# SparkFun_SSOP28-DIP-Adapter-v12.net
KiCad netlist of a schematic drawn in EAGLE
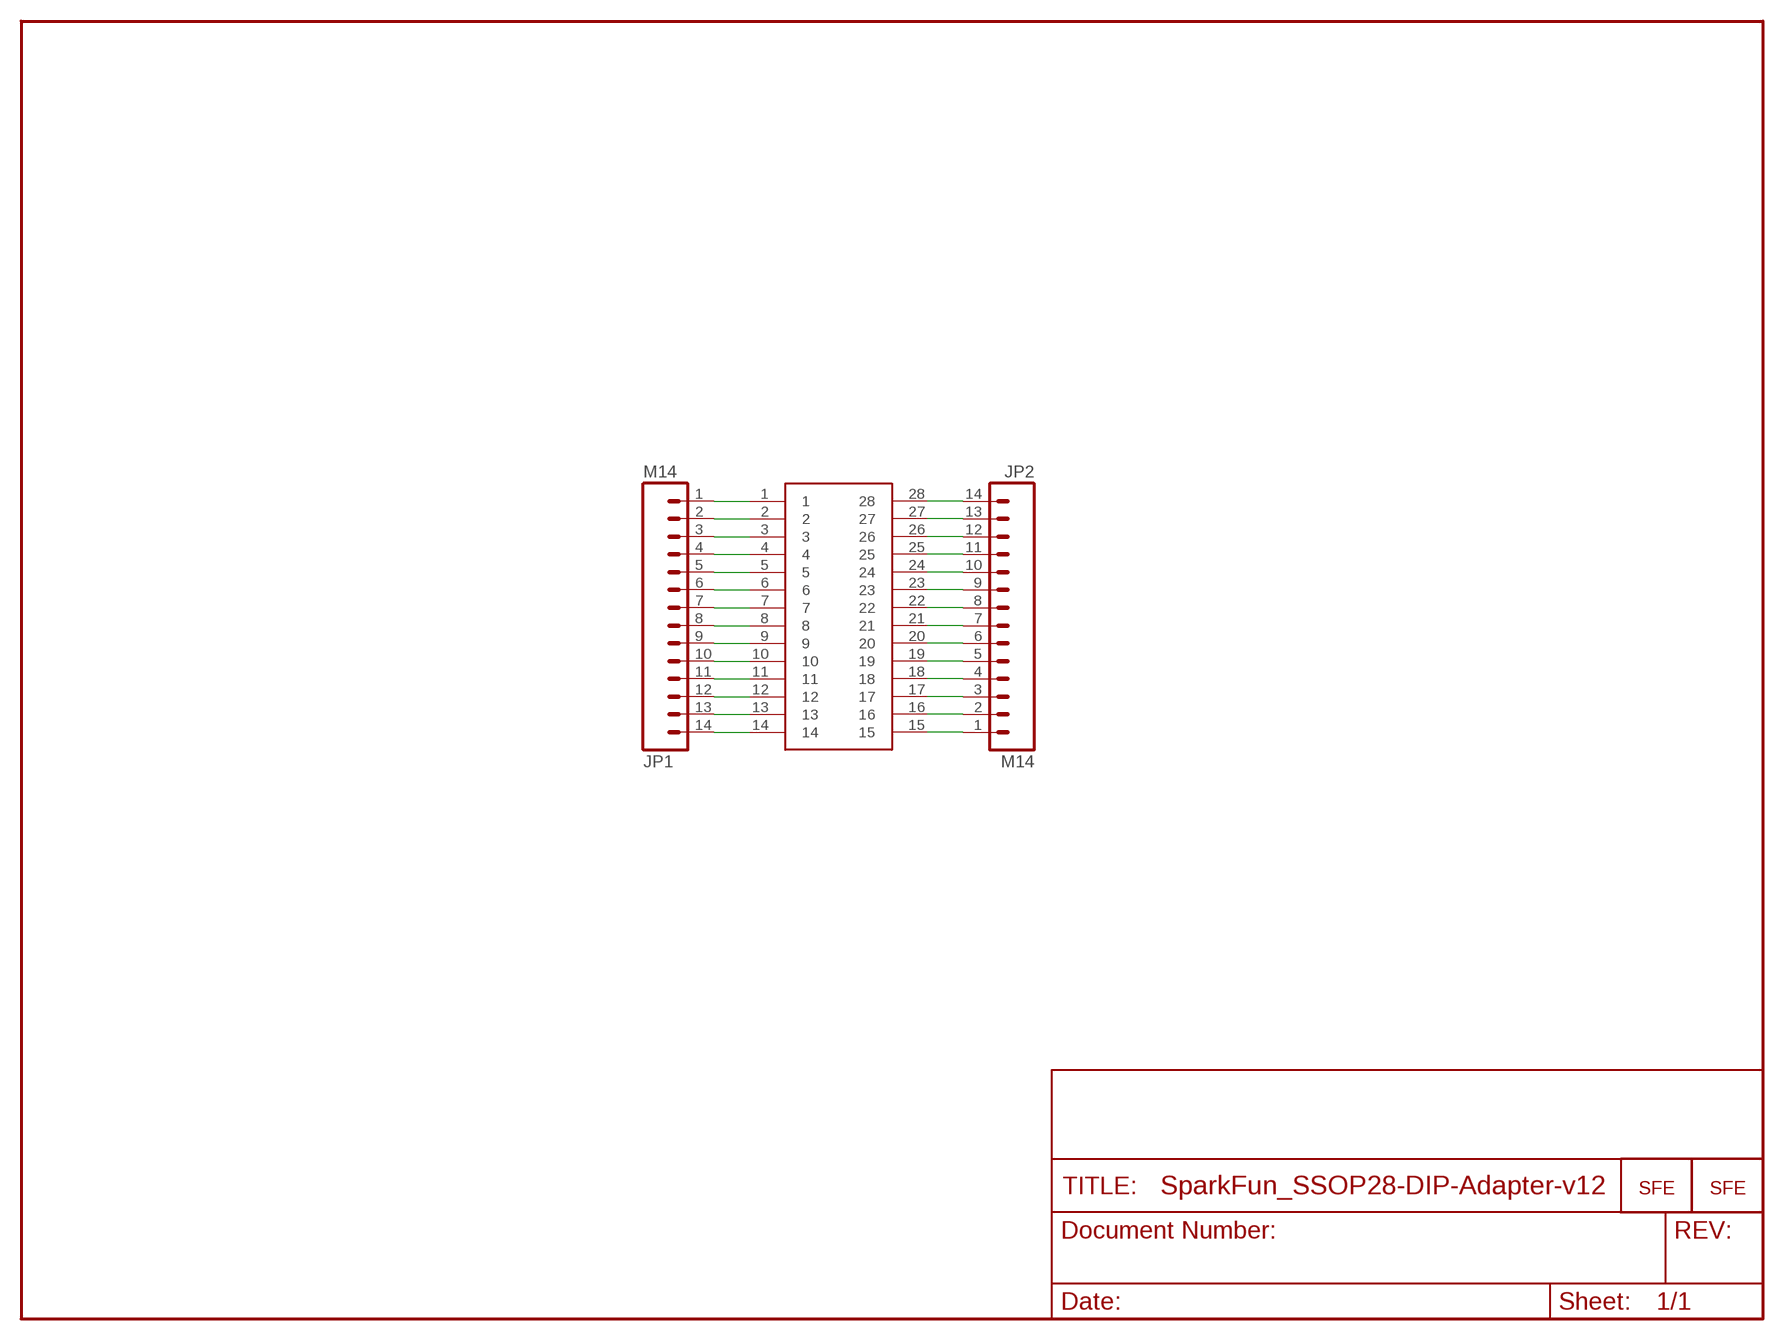
[diagram p0: schematic, sheet 1]

(export (version "E")
  (design (tool "Eeschema 10.0.6"))
  (components
    (comp (ref "JP1")
      (value "M14")
      (footprint "eagle-import:1X14")
      (libsource (lib "eagle-import") (part "M14"))
    )
    (comp (ref "JP2")
      (value "M14")
      (footprint "eagle-import:1X14")
      (libsource (lib "eagle-import") (part "M14"))
    )
    (comp (ref "U$1")
      (value "LOGO-SFESK")
      (footprint "eagle-import:SFE-LOGO-FLAME")
      (libsource (lib "eagle-import") (part "LOGO-SFESK"))
    )
    (comp (ref "U$2")
      (value "SSOP28")
      (footprint "eagle-import:SSOP28DB")
      (libsource (lib "eagle-import") (part "SSOP28"))
    )
    (comp (ref "U$5")
      (value "LOGO-SFENEW")
      (footprint "eagle-import:SFE-NEW-WEBLOGO")
      (libsource (lib "eagle-import") (part "LOGO-SFENEW"))
    )
  )
  (nets
    (net (code "1") (name "Net-(JP1-Pad1)") (class "Default")
      (node (ref "JP1") (pin "1") (pinfunction "1_1") (pintype "passive"))
      (node (ref "U$2") (pin "1") (pinfunction "1_1") (pintype "bidirectional"))
    )
    (net (code "2") (name "Net-(JP1-Pad2)") (class "Default")
      (node (ref "JP1") (pin "2") (pinfunction "2_2") (pintype "passive"))
      (node (ref "U$2") (pin "2") (pinfunction "2_2") (pintype "bidirectional"))
    )
    (net (code "3") (name "Net-(JP1-Pad3)") (class "Default")
      (node (ref "JP1") (pin "3") (pinfunction "3_3") (pintype "passive"))
      (node (ref "U$2") (pin "3") (pinfunction "3_3") (pintype "bidirectional"))
    )
    (net (code "4") (name "Net-(JP1-Pad4)") (class "Default")
      (node (ref "JP1") (pin "4") (pinfunction "4_4") (pintype "passive"))
      (node (ref "U$2") (pin "4") (pinfunction "4_4") (pintype "bidirectional"))
    )
    (net (code "5") (name "Net-(JP1-Pad5)") (class "Default")
      (node (ref "JP1") (pin "5") (pinfunction "5_5") (pintype "passive"))
      (node (ref "U$2") (pin "5") (pinfunction "5_5") (pintype "bidirectional"))
    )
    (net (code "6") (name "Net-(JP1-Pad6)") (class "Default")
      (node (ref "JP1") (pin "6") (pinfunction "6_6") (pintype "passive"))
      (node (ref "U$2") (pin "6") (pinfunction "6_6") (pintype "bidirectional"))
    )
    (net (code "7") (name "Net-(JP1-Pad7)") (class "Default")
      (node (ref "JP1") (pin "7") (pinfunction "7_7") (pintype "passive"))
      (node (ref "U$2") (pin "7") (pinfunction "7_7") (pintype "bidirectional"))
    )
    (net (code "8") (name "Net-(JP1-Pad8)") (class "Default")
      (node (ref "JP1") (pin "8") (pinfunction "8_8") (pintype "passive"))
      (node (ref "U$2") (pin "8") (pinfunction "8_8") (pintype "bidirectional"))
    )
    (net (code "9") (name "Net-(JP1-Pad9)") (class "Default")
      (node (ref "JP1") (pin "9") (pinfunction "9_9") (pintype "passive"))
      (node (ref "U$2") (pin "9") (pinfunction "9_9") (pintype "bidirectional"))
    )
    (net (code "10") (name "Net-(JP1-Pad10)") (class "Default")
      (node (ref "JP1") (pin "10") (pinfunction "10_10") (pintype "passive"))
      (node (ref "U$2") (pin "10") (pinfunction "10_10") (pintype "bidirectional"))
    )
    (net (code "11") (name "Net-(JP1-Pad11)") (class "Default")
      (node (ref "JP1") (pin "11") (pinfunction "11_11") (pintype "passive"))
      (node (ref "U$2") (pin "11") (pinfunction "11_11") (pintype "bidirectional"))
    )
    (net (code "12") (name "Net-(JP1-Pad12)") (class "Default")
      (node (ref "JP1") (pin "12") (pinfunction "12_12") (pintype "passive"))
      (node (ref "U$2") (pin "12") (pinfunction "12_12") (pintype "bidirectional"))
    )
    (net (code "13") (name "Net-(JP1-Pad13)") (class "Default")
      (node (ref "JP1") (pin "13") (pinfunction "13_13") (pintype "passive"))
      (node (ref "U$2") (pin "13") (pinfunction "13_13") (pintype "bidirectional"))
    )
    (net (code "14") (name "Net-(JP1-Pad14)") (class "Default")
      (node (ref "JP1") (pin "14") (pinfunction "14_14") (pintype "passive"))
      (node (ref "U$2") (pin "14") (pinfunction "14_14") (pintype "bidirectional"))
    )
    (net (code "15") (name "Net-(JP2-Pad1)") (class "Default")
      (node (ref "JP2") (pin "1") (pinfunction "1_1") (pintype "passive"))
      (node (ref "U$2") (pin "15") (pinfunction "15_15") (pintype "bidirectional"))
    )
    (net (code "16") (name "Net-(JP2-Pad2)") (class "Default")
      (node (ref "JP2") (pin "2") (pinfunction "2_2") (pintype "passive"))
      (node (ref "U$2") (pin "16") (pinfunction "16_16") (pintype "bidirectional"))
    )
    (net (code "17") (name "Net-(JP2-Pad3)") (class "Default")
      (node (ref "JP2") (pin "3") (pinfunction "3_3") (pintype "passive"))
      (node (ref "U$2") (pin "17") (pinfunction "17_17") (pintype "bidirectional"))
    )
    (net (code "18") (name "Net-(JP2-Pad4)") (class "Default")
      (node (ref "JP2") (pin "4") (pinfunction "4_4") (pintype "passive"))
      (node (ref "U$2") (pin "18") (pinfunction "18_18") (pintype "bidirectional"))
    )
    (net (code "19") (name "Net-(JP2-Pad5)") (class "Default")
      (node (ref "JP2") (pin "5") (pinfunction "5_5") (pintype "passive"))
      (node (ref "U$2") (pin "19") (pinfunction "19_19") (pintype "bidirectional"))
    )
    (net (code "20") (name "Net-(JP2-Pad6)") (class "Default")
      (node (ref "JP2") (pin "6") (pinfunction "6_6") (pintype "passive"))
      (node (ref "U$2") (pin "20") (pinfunction "20_20") (pintype "bidirectional"))
    )
    (net (code "21") (name "Net-(JP2-Pad7)") (class "Default")
      (node (ref "JP2") (pin "7") (pinfunction "7_7") (pintype "passive"))
      (node (ref "U$2") (pin "21") (pinfunction "21_21") (pintype "bidirectional"))
    )
    (net (code "22") (name "Net-(JP2-Pad8)") (class "Default")
      (node (ref "JP2") (pin "8") (pinfunction "8_8") (pintype "passive"))
      (node (ref "U$2") (pin "22") (pinfunction "22_22") (pintype "bidirectional"))
    )
    (net (code "23") (name "Net-(JP2-Pad9)") (class "Default")
      (node (ref "JP2") (pin "9") (pinfunction "9_9") (pintype "passive"))
      (node (ref "U$2") (pin "23") (pinfunction "23_23") (pintype "bidirectional"))
    )
    (net (code "24") (name "Net-(JP2-Pad10)") (class "Default")
      (node (ref "JP2") (pin "10") (pinfunction "10_10") (pintype "passive"))
      (node (ref "U$2") (pin "24") (pinfunction "24_24") (pintype "bidirectional"))
    )
    (net (code "25") (name "Net-(JP2-Pad11)") (class "Default")
      (node (ref "JP2") (pin "11") (pinfunction "11_11") (pintype "passive"))
      (node (ref "U$2") (pin "25") (pinfunction "25_25") (pintype "bidirectional"))
    )
    (net (code "26") (name "Net-(JP2-Pad12)") (class "Default")
      (node (ref "JP2") (pin "12") (pinfunction "12_12") (pintype "passive"))
      (node (ref "U$2") (pin "26") (pinfunction "26_26") (pintype "bidirectional"))
    )
    (net (code "27") (name "Net-(JP2-Pad13)") (class "Default")
      (node (ref "JP2") (pin "13") (pinfunction "13_13") (pintype "passive"))
      (node (ref "U$2") (pin "27") (pinfunction "27_27") (pintype "bidirectional"))
    )
    (net (code "28") (name "Net-(JP2-Pad14)") (class "Default")
      (node (ref "JP2") (pin "14") (pinfunction "14_14") (pintype "passive"))
      (node (ref "U$2") (pin "28") (pinfunction "28_28") (pintype "bidirectional"))
    )
  )
)
